# fingertip_12line_outlined_2.net
KiCad netlist of a schematic drawn in EAGLE
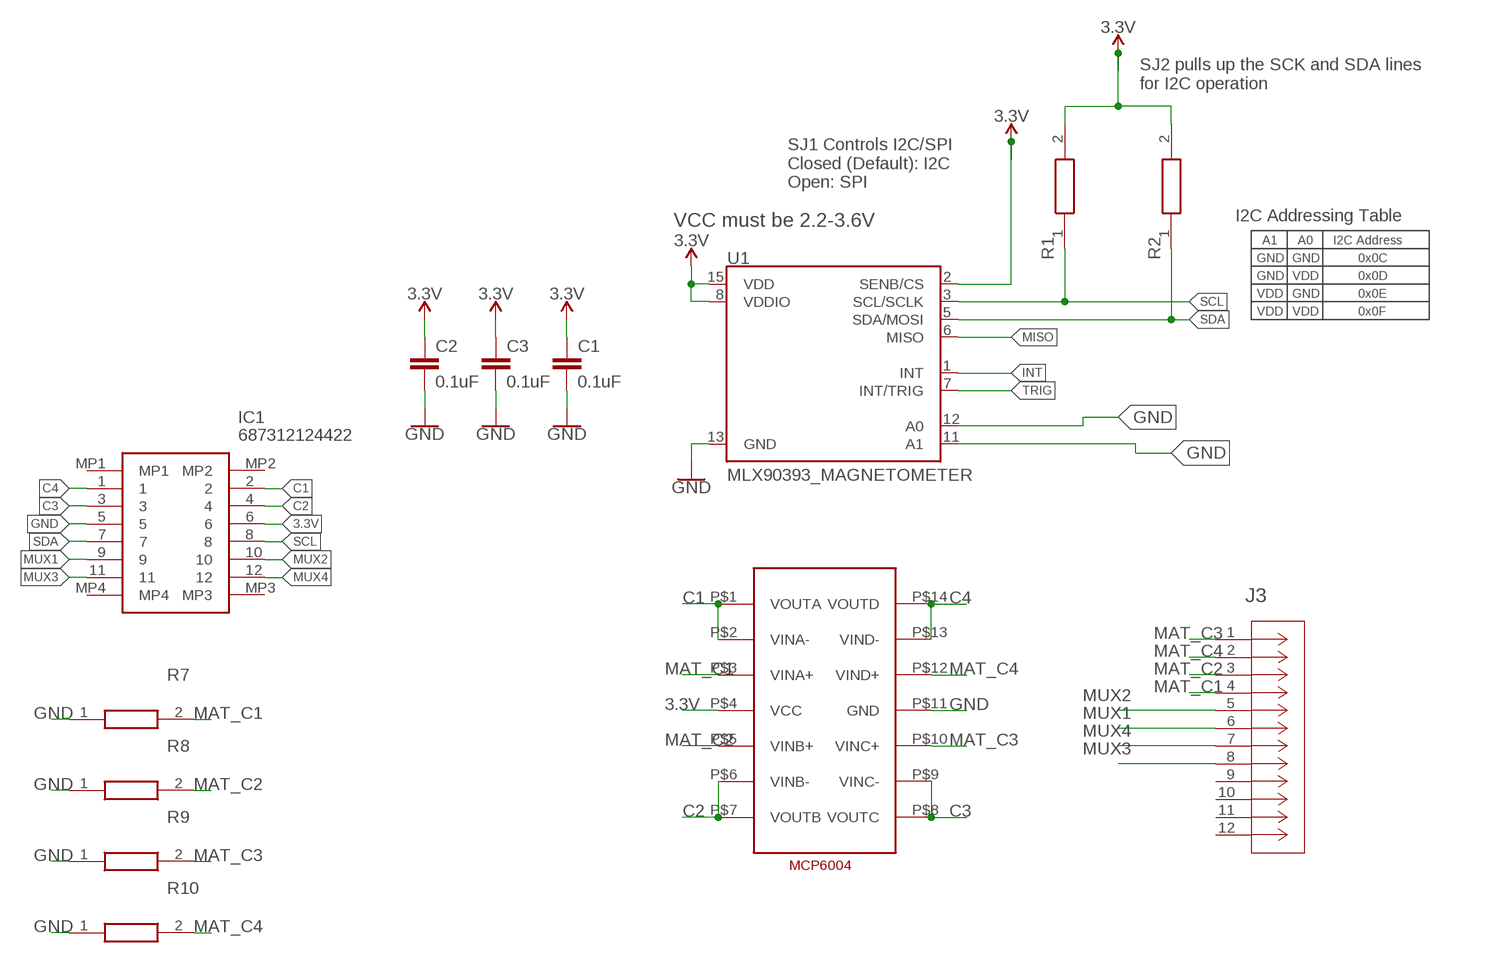
[diagram p0: schematic, sheet 1]

(export (version "E")
  (design (tool "Eeschema 10.0.6"))
  (components
    (comp (ref "C1")
      (value "0.1uF")
      (footprint "eagle-import:0402")
      (libsource (lib "eagle-import") (part "0.1UF-0402-16V-10%"))
    )
    (comp (ref "C2")
      (value "0.1uF")
      (footprint "eagle-import:0402")
      (libsource (lib "eagle-import") (part "0.1UF-0402-16V-10%"))
    )
    (comp (ref "C3")
      (value "0.1uF")
      (footprint "eagle-import:0402")
      (libsource (lib "eagle-import") (part "0.1UF-0402-16V-10%"))
    )
    (comp (ref "IC1")
      (value "687312124422")
      (footprint "eagle-import:687312124422")
      (fields (field (name "MOUSER_PART_NUMBER") "710-687312124422"))
      (libsource (lib "eagle-import") (part "687312124422"))
    )
    (comp (ref "J3")
      (value "FH12-8S-1SV(55)")
      (footprint "eagle-import:CON8_1X8_DUTB1_HRS_HIR")
      (fields (field (name "COPYRIGHT") "Copyright (C) 2018 Accelerated Designs. All rights reserved"))
      (libsource (lib "eagle-import") (part "FH12-8S-1SV(55)"))
    )
    (comp (ref "R1")
      (value "ERJ-S02J103X")
      (footprint "eagle-import:RESC1005X40N")
      (libsource (lib "eagle-import") (part "ERJ-S02J103X"))
    )
    (comp (ref "R2")
      (value "ERJ-S02J103X")
      (footprint "eagle-import:RESC1005X40N")
      (libsource (lib "eagle-import") (part "ERJ-S02J103X"))
    )
    (comp (ref "R7")
      (value "ERJ-S02J103X")
      (footprint "eagle-import:RESC1005X40N")
      (libsource (lib "eagle-import") (part "ERJ-S02J103X"))
    )
    (comp (ref "R8")
      (value "ERJ-S02J103X")
      (footprint "eagle-import:RESC1005X40N")
      (libsource (lib "eagle-import") (part "ERJ-S02J103X"))
    )
    (comp (ref "R9")
      (value "ERJ-S02J103X")
      (footprint "eagle-import:RESC1005X40N")
      (libsource (lib "eagle-import") (part "ERJ-S02J103X"))
    )
    (comp (ref "R10")
      (value "ERJ-S02J103X")
      (footprint "eagle-import:RESC1005X40N")
      (libsource (lib "eagle-import") (part "ERJ-S02J103X"))
    )
    (comp (ref "U$2")
      (value "DECADE-MCP6004")
      (footprint "eagle-import:DECADE-MCP6003")
      (libsource (lib "eagle-import") (part "DECADE-MCP6004"))
    )
    (comp (ref "U1")
      (value "MLX90393_MAGNETOMETER")
      (footprint "eagle-import:QFN-16_WITH_AXIES")
      (libsource (lib "eagle-import") (part "MLX90393_MAGNETOMETER"))
    )
  )
  (nets
    (net (code "1") (name "/MAT_C1") (class "Default")
      (node (ref "J3") (pin "4") (pinfunction "4_4") (pintype "passive"))
      (node (ref "R7") (pin "2") (pinfunction "2_2") (pintype "bidirectional"))
      (node (ref "U$2") (pin "P$3") (pinfunction "VINA+_P$3") (pintype "bidirectional"))
    )
    (net (code "2") (name "/MAT_C2") (class "Default")
      (node (ref "J3") (pin "3") (pinfunction "3_3") (pintype "passive"))
      (node (ref "R8") (pin "2") (pinfunction "2_2") (pintype "bidirectional"))
      (node (ref "U$2") (pin "P$5") (pinfunction "VINB+_P$5") (pintype "bidirectional"))
    )
    (net (code "3") (name "/MAT_C3") (class "Default")
      (node (ref "J3") (pin "1") (pinfunction "1_1") (pintype "passive"))
      (node (ref "R9") (pin "2") (pinfunction "2_2") (pintype "bidirectional"))
      (node (ref "U$2") (pin "P$10") (pinfunction "VINC+_P$10") (pintype "bidirectional"))
    )
    (net (code "4") (name "/MAT_C4") (class "Default")
      (node (ref "J3") (pin "2") (pinfunction "2_2") (pintype "passive"))
      (node (ref "R10") (pin "2") (pinfunction "2_2") (pintype "bidirectional"))
      (node (ref "U$2") (pin "P$12") (pinfunction "VIND+_P$12") (pintype "bidirectional"))
    )
    (net (code "5") (name "3.3V") (class "Default")
      (node (ref "C1") (pin "1") (pinfunction "1_1") (pintype "passive"))
      (node (ref "C2") (pin "1") (pinfunction "1_1") (pintype "passive"))
      (node (ref "C3") (pin "1") (pinfunction "1_1") (pintype "passive"))
      (node (ref "IC1") (pin "6") (pinfunction "6_6") (pintype "bidirectional"))
      (node (ref "R1") (pin "2") (pinfunction "2_2") (pintype "bidirectional"))
      (node (ref "R2") (pin "2") (pinfunction "2_2") (pintype "bidirectional"))
      (node (ref "U$2") (pin "P$4") (pinfunction "VCC_P$4") (pintype "bidirectional"))
      (node (ref "U1") (pin "15") (pinfunction "VDD_15") (pintype "bidirectional"))
      (node (ref "U1") (pin "2") (pinfunction "SENB/CS_2") (pintype "bidirectional"))
      (node (ref "U1") (pin "8") (pinfunction "VDDIO_8") (pintype "bidirectional"))
    )
    (net (code "6") (name "C1") (class "Default")
      (node (ref "IC1") (pin "2") (pinfunction "2_2") (pintype "bidirectional"))
      (node (ref "U$2") (pin "P$1") (pinfunction "VOUTA_P$1") (pintype "bidirectional"))
      (node (ref "U$2") (pin "P$2") (pinfunction "VINA-_P$2") (pintype "bidirectional"))
    )
    (net (code "7") (name "C2") (class "Default")
      (node (ref "IC1") (pin "4") (pinfunction "4_4") (pintype "bidirectional"))
      (node (ref "U$2") (pin "P$6") (pinfunction "VINB-_P$6") (pintype "bidirectional"))
      (node (ref "U$2") (pin "P$7") (pinfunction "VOUTB_P$7") (pintype "bidirectional"))
    )
    (net (code "8") (name "C3") (class "Default")
      (node (ref "IC1") (pin "3") (pinfunction "3_3") (pintype "bidirectional"))
      (node (ref "U$2") (pin "P$8") (pinfunction "VOUTC_P$8") (pintype "bidirectional"))
      (node (ref "U$2") (pin "P$9") (pinfunction "VINC-_P$9") (pintype "bidirectional"))
    )
    (net (code "9") (name "C4") (class "Default")
      (node (ref "IC1") (pin "1") (pinfunction "1_1") (pintype "bidirectional"))
      (node (ref "U$2") (pin "P$13") (pinfunction "VIND-_P$13") (pintype "bidirectional"))
      (node (ref "U$2") (pin "P$14") (pinfunction "VOUTD_P$14") (pintype "bidirectional"))
    )
    (net (code "10") (name "GND") (class "Default")
      (node (ref "C1") (pin "2") (pinfunction "2_2") (pintype "passive"))
      (node (ref "C2") (pin "2") (pinfunction "2_2") (pintype "passive"))
      (node (ref "C3") (pin "2") (pinfunction "2_2") (pintype "passive"))
      (node (ref "IC1") (pin "5") (pinfunction "5_5") (pintype "bidirectional"))
      (node (ref "R10") (pin "1") (pinfunction "1_1") (pintype "bidirectional"))
      (node (ref "R7") (pin "1") (pinfunction "1_1") (pintype "bidirectional"))
      (node (ref "R8") (pin "1") (pinfunction "1_1") (pintype "bidirectional"))
      (node (ref "R9") (pin "1") (pinfunction "1_1") (pintype "bidirectional"))
      (node (ref "U$2") (pin "P$11") (pinfunction "GND_P$11") (pintype "bidirectional"))
      (node (ref "U1") (pin "11") (pinfunction "A1_11") (pintype "bidirectional"))
      (node (ref "U1") (pin "12") (pinfunction "A0_12") (pintype "bidirectional"))
      (node (ref "U1") (pin "13") (pinfunction "GND_13") (pintype "bidirectional"))
    )
    (net (code "11") (name "INT") (class "Default")
      (node (ref "U1") (pin "1") (pinfunction "INT_1") (pintype "bidirectional"))
    )
    (net (code "12") (name "MISO") (class "Default")
      (node (ref "U1") (pin "6") (pinfunction "MISO_6") (pintype "bidirectional"))
    )
    (net (code "13") (name "MUX1") (class "Default")
      (node (ref "IC1") (pin "9") (pinfunction "9_9") (pintype "bidirectional"))
      (node (ref "J3") (pin "6") (pinfunction "6_6") (pintype "passive"))
    )
    (net (code "14") (name "MUX2") (class "Default")
      (node (ref "IC1") (pin "10") (pinfunction "10_10") (pintype "bidirectional"))
      (node (ref "J3") (pin "5") (pinfunction "5_5") (pintype "passive"))
    )
    (net (code "15") (name "MUX3") (class "Default")
      (node (ref "IC1") (pin "11") (pinfunction "11_11") (pintype "bidirectional"))
      (node (ref "J3") (pin "8") (pinfunction "8_8") (pintype "passive"))
    )
    (net (code "16") (name "MUX4") (class "Default")
      (node (ref "IC1") (pin "12") (pinfunction "12_12") (pintype "bidirectional"))
      (node (ref "J3") (pin "7") (pinfunction "7_7") (pintype "passive"))
    )
    (net (code "17") (name "SCL") (class "Default")
      (node (ref "IC1") (pin "8") (pinfunction "8_8") (pintype "bidirectional"))
      (node (ref "R1") (pin "1") (pinfunction "1_1") (pintype "bidirectional"))
      (node (ref "U1") (pin "3") (pinfunction "SCL/SCLK_3") (pintype "bidirectional"))
    )
    (net (code "18") (name "SDA") (class "Default")
      (node (ref "IC1") (pin "7") (pinfunction "7_7") (pintype "bidirectional"))
      (node (ref "R2") (pin "1") (pinfunction "1_1") (pintype "bidirectional"))
      (node (ref "U1") (pin "5") (pinfunction "SDA/MOSI_5") (pintype "bidirectional"))
    )
    (net (code "19") (name "TRIG") (class "Default")
      (node (ref "U1") (pin "7") (pinfunction "INT/TRIG_7") (pintype "bidirectional"))
    )
    (net (code "20") (name "unconnected-(IC1-PadMP1)") (class "Default")
      (node (ref "IC1") (pin "MP1") (pinfunction "MP1_MP1") (pintype "bidirectional"))
    )
    (net (code "21") (name "unconnected-(IC1-PadMP2)") (class "Default")
      (node (ref "IC1") (pin "MP2") (pinfunction "MP2_MP2") (pintype "bidirectional"))
    )
    (net (code "22") (name "unconnected-(IC1-PadMP3)") (class "Default")
      (node (ref "IC1") (pin "MP3") (pinfunction "MP3_MP3") (pintype "bidirectional"))
    )
    (net (code "23") (name "unconnected-(IC1-PadMP4)") (class "Default")
      (node (ref "IC1") (pin "MP4") (pinfunction "MP4_MP4") (pintype "bidirectional"))
    )
    (net (code "24") (name "unconnected-(J3-Pad9)") (class "Default")
      (node (ref "J3") (pin "9") (pinfunction "9_9") (pintype "passive"))
    )
    (net (code "25") (name "unconnected-(J3-Pad10)") (class "Default")
      (node (ref "J3") (pin "10") (pinfunction "10_10") (pintype "passive"))
    )
    (net (code "26") (name "unconnected-(J3-Pad11)") (class "Default")
      (node (ref "J3") (pin "11") (pinfunction "11_11") (pintype "passive"))
    )
    (net (code "27") (name "unconnected-(J3-Pad12)") (class "Default")
      (node (ref "J3") (pin "12") (pinfunction "12_12") (pintype "passive"))
    )
  )
)
